# SRAM.net
KiCad netlist of a schematic drawn in Altium Designer
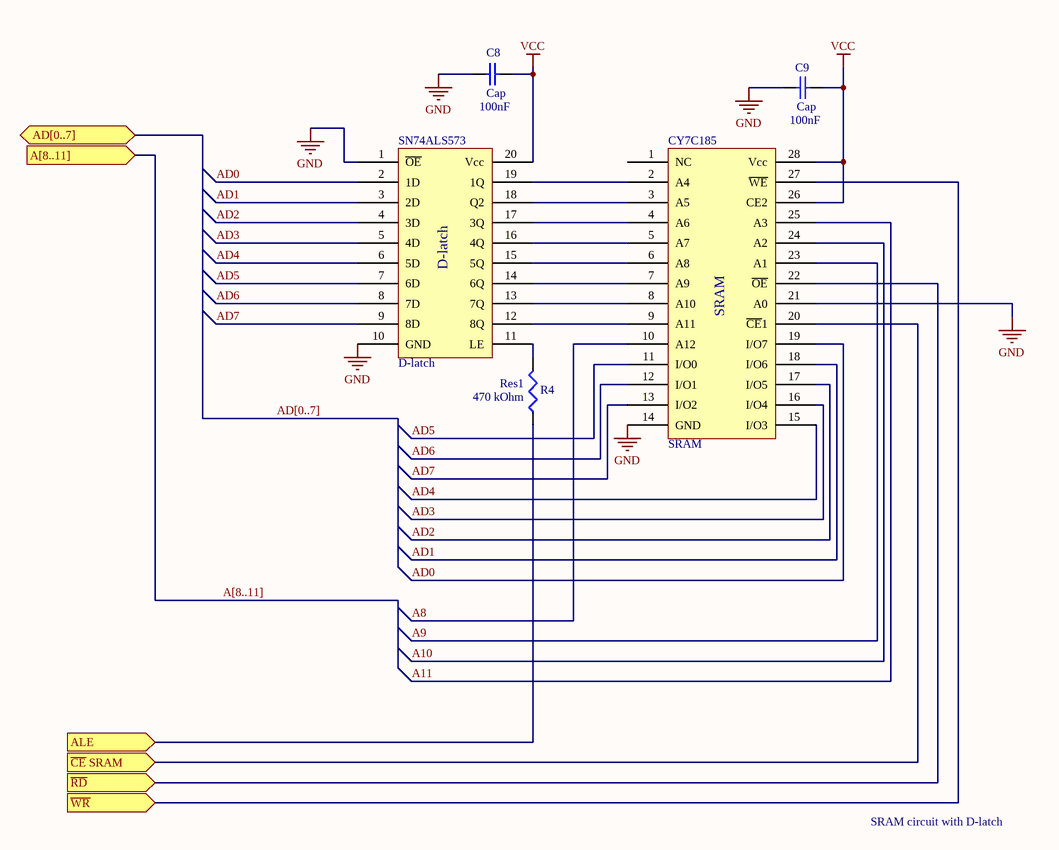
[diagram p0: SRAM.SchDoc]

(export (version "E")
  (design (tool "Eeschema 10.0.6"))
  (components
    (comp (ref "C8")
      (value "Cap")
      (footprint "C1210")
      (description "Capacitor (Semiconductor SIM Model)")
      (fields (field (name "ALTIUM_VALUE") "100nF") (field (name "PUBLISHER") "Altium Limited"))
      (libsource (lib "Miscellaneous Devices") (part "Cap Semi"))
    )
    (comp (ref "C9")
      (value "Cap")
      (footprint "C1210")
      (description "Capacitor (Semiconductor SIM Model)")
      (fields (field (name "ALTIUM_VALUE") "100nF") (field (name "PUBLISHER") "Altium Limited"))
      (libsource (lib "Miscellaneous Devices") (part "Cap Semi"))
    )
    (comp (ref "CY7C185")
      (value "SRAM")
      (footprint "CY7C185 SOIC 28-PIN")
      (description "SRAM - Static Random Access Memory")
      (libsource (lib "IIDKLib") (part "CY7C185"))
    )
    (comp (ref "R4")
      (value "Res1")
      (footprint "14-1210")
      (description "Resistor")
      (fields (field (name "ALTIUM_VALUE") "470 kOhm") (field (name "PUBLISHER") "Altium Limited"))
      (libsource (lib "Miscellaneous Devices") (part "Res3"))
    )
    (comp (ref "SN74ALS573")
      (value "D-latch")
      (footprint "IIDKLib:D-Latch SOIC 20-PIN")
      (description "D-Latch")
      (libsource (lib "IIDKLib") (part "SN74ALS573"))
    )
  )
  (nets
    (net (code "1") (name "/A8") (class "Default")
      (node (ref "CY7C185") (pin "10") (pinfunction "A12_10") (pintype "passive"))
    )
    (net (code "2") (name "/A9") (class "Default")
      (node (ref "CY7C185") (pin "23") (pinfunction "A1_23") (pintype "passive"))
    )
    (net (code "3") (name "/A10") (class "Default")
      (node (ref "CY7C185") (pin "24") (pinfunction "A2_24") (pintype "passive"))
    )
    (net (code "4") (name "/A11") (class "Default")
      (node (ref "CY7C185") (pin "25") (pinfunction "A3_25") (pintype "passive"))
    )
    (net (code "5") (name "/AD0") (class "Default")
      (node (ref "CY7C185") (pin "19") (pinfunction "I/O7_19") (pintype "passive"))
      (node (ref "SN74ALS573") (pin "2") (pinfunction "1D_2") (pintype "passive"))
    )
    (net (code "6") (name "/AD1") (class "Default")
      (node (ref "CY7C185") (pin "18") (pinfunction "I/O6_18") (pintype "passive"))
      (node (ref "SN74ALS573") (pin "3") (pinfunction "2D_3") (pintype "passive"))
    )
    (net (code "7") (name "/AD2") (class "Default")
      (node (ref "CY7C185") (pin "17") (pinfunction "I/O5_17") (pintype "passive"))
      (node (ref "SN74ALS573") (pin "4") (pinfunction "3D_4") (pintype "passive"))
    )
    (net (code "8") (name "/AD3") (class "Default")
      (node (ref "CY7C185") (pin "16") (pinfunction "I/O4_16") (pintype "passive"))
      (node (ref "SN74ALS573") (pin "5") (pinfunction "4D_5") (pintype "passive"))
    )
    (net (code "9") (name "/AD4") (class "Default")
      (node (ref "CY7C185") (pin "15") (pinfunction "I/O3_15") (pintype "passive"))
      (node (ref "SN74ALS573") (pin "6") (pinfunction "5D_6") (pintype "passive"))
    )
    (net (code "10") (name "/AD5") (class "Default")
      (node (ref "CY7C185") (pin "11") (pinfunction "I/O0_11") (pintype "passive"))
      (node (ref "SN74ALS573") (pin "7") (pinfunction "6D_7") (pintype "passive"))
    )
    (net (code "11") (name "/AD6") (class "Default")
      (node (ref "CY7C185") (pin "12") (pinfunction "I/O1_12") (pintype "passive"))
      (node (ref "SN74ALS573") (pin "8") (pinfunction "7D_8") (pintype "passive"))
    )
    (net (code "12") (name "/AD7") (class "Default")
      (node (ref "CY7C185") (pin "13") (pinfunction "I/O2_13") (pintype "passive"))
      (node (ref "SN74ALS573") (pin "9") (pinfunction "8D_9") (pintype "passive"))
    )
    (net (code "14") (name "/ALE") (class "Default")
      (node (ref "R4") (pin "2") (pinfunction "2_2") (pintype "passive"))
    )
    (net (code "16") (name "/~{CE} SRAM") (class "Default")
      (node (ref "CY7C185") (pin "20") (pinfunction "~{CE}1_20") (pintype "passive"))
    )
    (net (code "17") (name "/~{RD}") (class "Default")
      (node (ref "CY7C185") (pin "22") (pinfunction "~{OE}_22") (pintype "passive"))
    )
    (net (code "18") (name "/~{WR}") (class "Default")
      (node (ref "CY7C185") (pin "27") (pinfunction "~{WE}_27") (pintype "passive"))
    )
    (net (code "19") (name "GND") (class "Default")
      (node (ref "C8") (pin "2") (pinfunction "2_2") (pintype "passive"))
      (node (ref "C9") (pin "2") (pinfunction "2_2") (pintype "passive"))
      (node (ref "CY7C185") (pin "14") (pinfunction "GND_14") (pintype "power_in"))
      (node (ref "CY7C185") (pin "21") (pinfunction "A0_21") (pintype "passive"))
      (node (ref "SN74ALS573") (pin "1") (pinfunction "~{OE}_1") (pintype "passive"))
      (node (ref "SN74ALS573") (pin "10") (pinfunction "GND_10") (pintype "power_in"))
    )
    (net (code "20") (name "Net-(CY7C185-A4)") (class "Default")
      (node (ref "CY7C185") (pin "2") (pinfunction "A4_2") (pintype "passive"))
      (node (ref "SN74ALS573") (pin "19") (pinfunction "1Q_19") (pintype "passive"))
    )
    (net (code "21") (name "Net-(CY7C185-A5)") (class "Default")
      (node (ref "CY7C185") (pin "3") (pinfunction "A5_3") (pintype "passive"))
      (node (ref "SN74ALS573") (pin "18") (pinfunction "Q2_18") (pintype "passive"))
    )
    (net (code "22") (name "Net-(CY7C185-A6)") (class "Default")
      (node (ref "CY7C185") (pin "4") (pinfunction "A6_4") (pintype "passive"))
      (node (ref "SN74ALS573") (pin "17") (pinfunction "3Q_17") (pintype "passive"))
    )
    (net (code "23") (name "Net-(CY7C185-A7)") (class "Default")
      (node (ref "CY7C185") (pin "5") (pinfunction "A7_5") (pintype "passive"))
      (node (ref "SN74ALS573") (pin "16") (pinfunction "4Q_16") (pintype "passive"))
    )
    (net (code "24") (name "Net-(CY7C185-A8)") (class "Default")
      (node (ref "CY7C185") (pin "6") (pinfunction "A8_6") (pintype "passive"))
      (node (ref "SN74ALS573") (pin "15") (pinfunction "5Q_15") (pintype "passive"))
    )
    (net (code "25") (name "Net-(CY7C185-A9)") (class "Default")
      (node (ref "CY7C185") (pin "7") (pinfunction "A9_7") (pintype "passive"))
      (node (ref "SN74ALS573") (pin "14") (pinfunction "6Q_14") (pintype "passive"))
    )
    (net (code "26") (name "Net-(CY7C185-A10)") (class "Default")
      (node (ref "CY7C185") (pin "8") (pinfunction "A10_8") (pintype "passive"))
      (node (ref "SN74ALS573") (pin "13") (pinfunction "7Q_13") (pintype "passive"))
    )
    (net (code "27") (name "Net-(CY7C185-A11)") (class "Default")
      (node (ref "CY7C185") (pin "9") (pinfunction "A11_9") (pintype "passive"))
      (node (ref "SN74ALS573") (pin "12") (pinfunction "8Q_12") (pintype "passive"))
    )
    (net (code "28") (name "Net-(SN74ALS573-LE)") (class "Default")
      (node (ref "R4") (pin "1") (pinfunction "1_1") (pintype "passive"))
      (node (ref "SN74ALS573") (pin "11") (pinfunction "LE_11") (pintype "passive"))
    )
    (net (code "29") (name "VCC") (class "Default")
      (node (ref "C8") (pin "1") (pinfunction "1_1") (pintype "passive"))
      (node (ref "C9") (pin "1") (pinfunction "1_1") (pintype "passive"))
      (node (ref "CY7C185") (pin "26") (pinfunction "CE2_26") (pintype "passive"))
      (node (ref "CY7C185") (pin "28") (pinfunction "Vcc_28") (pintype "power_in"))
      (node (ref "SN74ALS573") (pin "20") (pinfunction "Vcc_20") (pintype "power_in"))
    )
    (net (code "30") (name "unconnected-(CY7C185-NC-Pad1)") (class "Default")
      (node (ref "CY7C185") (pin "1") (pinfunction "NC_1") (pintype "passive"))
    )
  )
)
